# drone.net
KiCad netlist of a schematic drawn in Altium Designer
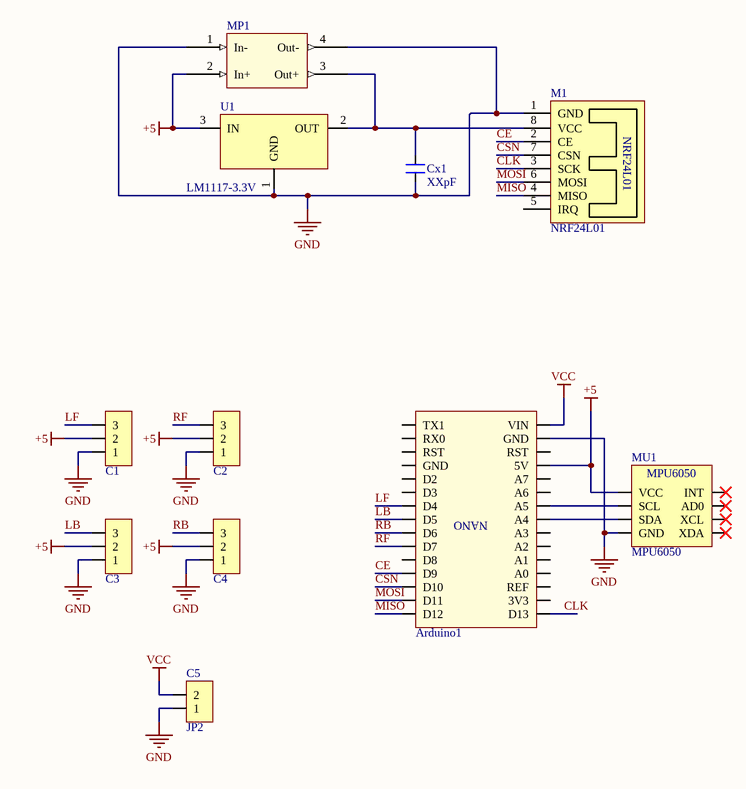
[diagram p0: drone.SchDoc]

(export (version "E")
  (design (tool "Eeschema 10.0.6"))
  (components
    (comp (ref "Arduino1")
      (value "Arduino Nano")
      (footprint "Arduino Nano")
      (description "Arduino NANO")
      (libsource (lib "LIBRARY") (part "Arduino Nano"))
    )
    (comp (ref "C1")
      (value "JP3")
      (footprint "JP3-C1T")
      (description "WR-PHD 2.54 mm Angled Socket Header")
      (fields
        (field (name "MANUFACTURER") "Würth Elektronik eiSos GmbH")
        (field (name "PARTNO") "613003143121")
        (field (name "CREATED BY") "Karrer Zheng")
      )
      (libsource (lib "LIBRARY") (part "JP3"))
    )
    (comp (ref "C2")
      (value "JP3")
      (footprint "JP3-C1T")
      (description "WR-PHD 2.54 mm Angled Socket Header")
      (fields
        (field (name "MANUFACTURER") "Würth Elektronik eiSos GmbH")
        (field (name "PARTNO") "613003143121")
        (field (name "CREATED BY") "Karrer Zheng")
      )
      (libsource (lib "LIBRARY") (part "JP3"))
    )
    (comp (ref "C3")
      (value "JP3")
      (footprint "JP3-C1T")
      (description "WR-PHD 2.54 mm Angled Socket Header")
      (fields
        (field (name "MANUFACTURER") "Würth Elektronik eiSos GmbH")
        (field (name "PARTNO") "613003143121")
        (field (name "CREATED BY") "Karrer Zheng")
      )
      (libsource (lib "LIBRARY") (part "JP3"))
    )
    (comp (ref "C4")
      (value "JP3")
      (footprint "JP3-C1T")
      (description "WR-PHD 2.54 mm Angled Socket Header")
      (fields
        (field (name "MANUFACTURER") "Würth Elektronik eiSos GmbH")
        (field (name "PARTNO") "613003143121")
        (field (name "CREATED BY") "Karrer Zheng")
      )
      (libsource (lib "LIBRARY") (part "JP3"))
    )
    (comp (ref "C5")
      (value "JP2")
      (footprint "JP2-C1T")
      (description "WR-PHD 2.54 mm Angled Socket Header")
      (fields
        (field (name "MANUFACTURER") "Würth Elektronik eiSos GmbH")
        (field (name "PARTNO") "613002143121")
        (field (name "CREATED BY") "Karrer Zheng")
      )
      (libsource (lib "LIBRARY") (part "JP2"))
    )
    (comp (ref "Cx1") (value "XXpF") (footprint "CN-SMD-1206") (libsource (lib "LIBRARY") (part "CN")))
    (comp (ref "M1") (value "NRF24L01") (footprint "NRF24L01") (libsource (lib "LIBRARY") (part "NRF24L01")))
    (comp (ref "MP1")
      (value "MP2307 DC-DC Switching Buck Step-Down Module")
      (footprint "Mini360")
      (libsource (lib "0503") (part "MP2307 Module"))
    )
    (comp (ref "MU1")
      (value "MPU6050")
      (footprint "MPU6050")
      (fields
        (field (name "MANUFACTURER") "Würth Elektronik eiSos GmbH")
        (field (name "PARTNO") "613004143121")
        (field (name "CREATED BY") "Karrer Zheng")
      )
      (libsource (lib "LIBRARY") (part "MPU6050"))
    )
    (comp (ref "U1")
      (value "LM1117-3.3V")
      (footprint "SOT223")
      (description "800mA Low-Dropout Linear Regulator")
      (fields (field (name "CREATOR") "Nguyen Ba Bien"))
      (libsource (lib "LIBRARY") (part "LM1117"))
    )
  )
  (nets
    (net (code "1") (name "+5") (class "Default")
      (node (ref "Arduino1") (pin "5V") (pinfunction "5V_5V") (pintype "passive"))
      (node (ref "C1") (pin "2") (pinfunction "2_2") (pintype "passive"))
      (node (ref "C2") (pin "2") (pinfunction "2_2") (pintype "passive"))
      (node (ref "C3") (pin "2") (pinfunction "2_2") (pintype "passive"))
      (node (ref "C4") (pin "2") (pinfunction "2_2") (pintype "passive"))
      (node (ref "MP1") (pin "2") (pinfunction "In+_2") (pintype "input"))
      (node (ref "MU1") (pin "1") (pinfunction "VCC_1") (pintype "passive"))
      (node (ref "U1") (pin "3") (pinfunction "IN_3") (pintype "passive"))
    )
    (net (code "2") (name "/CE") (class "Default")
      (node (ref "Arduino1") (pin "D9") (pinfunction "D9_D9") (pintype "passive"))
      (node (ref "M1") (pin "2") (pinfunction "CE_2") (pintype "passive"))
    )
    (net (code "3") (name "/CLK") (class "Default")
      (node (ref "Arduino1") (pin "D13") (pinfunction "D13_D13") (pintype "passive"))
      (node (ref "M1") (pin "3") (pinfunction "SCK_3") (pintype "passive"))
    )
    (net (code "4") (name "/CSN") (class "Default")
      (node (ref "Arduino1") (pin "D10") (pinfunction "D10_D10") (pintype "passive"))
      (node (ref "M1") (pin "7") (pinfunction "CSN_7") (pintype "passive"))
    )
    (net (code "5") (name "/LB") (class "Default")
      (node (ref "Arduino1") (pin "D5") (pinfunction "D5_D5") (pintype "passive"))
      (node (ref "C3") (pin "3") (pinfunction "3_3") (pintype "passive"))
    )
    (net (code "6") (name "/LF") (class "Default")
      (node (ref "Arduino1") (pin "D4") (pinfunction "D4_D4") (pintype "passive"))
      (node (ref "C1") (pin "3") (pinfunction "3_3") (pintype "passive"))
    )
    (net (code "7") (name "/MISO") (class "Default")
      (node (ref "Arduino1") (pin "D12") (pinfunction "D12_D12") (pintype "passive"))
      (node (ref "M1") (pin "4") (pinfunction "MISO_4") (pintype "passive"))
    )
    (net (code "8") (name "/MOSI") (class "Default")
      (node (ref "Arduino1") (pin "D11") (pinfunction "D11_D11") (pintype "passive"))
      (node (ref "M1") (pin "6") (pinfunction "MOSI_6") (pintype "passive"))
    )
    (net (code "9") (name "/RB") (class "Default")
      (node (ref "Arduino1") (pin "D6") (pinfunction "D6_D6") (pintype "passive"))
      (node (ref "C4") (pin "3") (pinfunction "3_3") (pintype "passive"))
    )
    (net (code "10") (name "/RF") (class "Default")
      (node (ref "Arduino1") (pin "D7") (pinfunction "D7_D7") (pintype "passive"))
      (node (ref "C2") (pin "3") (pinfunction "3_3") (pintype "passive"))
    )
    (net (code "11") (name "GND") (class "Default")
      (node (ref "Arduino1") (pin "GND") (pinfunction "GND_GND") (pintype "passive"))
      (node (ref "C1") (pin "1") (pinfunction "1_1") (pintype "passive"))
      (node (ref "C2") (pin "1") (pinfunction "1_1") (pintype "passive"))
      (node (ref "C3") (pin "1") (pinfunction "1_1") (pintype "passive"))
      (node (ref "C4") (pin "1") (pinfunction "1_1") (pintype "passive"))
      (node (ref "C5") (pin "1") (pinfunction "1_1") (pintype "passive"))
      (node (ref "Cx1") (pin "1") (pinfunction "1_1") (pintype "passive"))
      (node (ref "M1") (pin "1") (pinfunction "GND_1") (pintype "passive"))
      (node (ref "MP1") (pin "1") (pinfunction "In-_1") (pintype "input"))
      (node (ref "MP1") (pin "4") (pinfunction "Out-_4") (pintype "output"))
      (node (ref "MU1") (pin "2") (pinfunction "GND_2") (pintype "passive"))
      (node (ref "U1") (pin "1") (pinfunction "GND_1") (pintype "passive"))
    )
    (net (code "12") (name "Net-(M1-VCC)") (class "Default")
      (node (ref "Cx1") (pin "2") (pinfunction "2_2") (pintype "passive"))
      (node (ref "M1") (pin "8") (pinfunction "VCC_8") (pintype "passive"))
      (node (ref "MP1") (pin "3") (pinfunction "Out+_3") (pintype "output"))
      (node (ref "U1") (pin "2") (pinfunction "OUT_2") (pintype "passive"))
    )
    (net (code "13") (name "Net-(MU1-SCL)") (class "Default")
      (node (ref "Arduino1") (pin "A5") (pinfunction "A5_A5") (pintype "passive"))
      (node (ref "MU1") (pin "3") (pinfunction "SCL_3") (pintype "passive"))
    )
    (net (code "14") (name "Net-(MU1-SDA)") (class "Default")
      (node (ref "Arduino1") (pin "A4") (pinfunction "A4_A4") (pintype "passive"))
      (node (ref "MU1") (pin "4") (pinfunction "SDA_4") (pintype "passive"))
    )
    (net (code "15") (name "VCC") (class "Default")
      (node (ref "Arduino1") (pin "VIN") (pinfunction "VIN_VIN") (pintype "passive"))
      (node (ref "C5") (pin "2") (pinfunction "2_2") (pintype "passive"))
    )
    (net (code "16") (name "unconnected-(Arduino1-Pad3V3)") (class "Default")
      (node (ref "Arduino1") (pin "3V3") (pinfunction "3V3_3V3") (pintype "passive"))
    )
    (net (code "17") (name "unconnected-(Arduino1-PadA0)") (class "Default")
      (node (ref "Arduino1") (pin "A0") (pinfunction "A0_A0") (pintype "passive"))
    )
    (net (code "18") (name "unconnected-(Arduino1-PadA1)") (class "Default")
      (node (ref "Arduino1") (pin "A1") (pinfunction "A1_A1") (pintype "passive"))
    )
    (net (code "19") (name "unconnected-(Arduino1-PadA2)") (class "Default")
      (node (ref "Arduino1") (pin "A2") (pinfunction "A2_A2") (pintype "passive"))
    )
    (net (code "20") (name "unconnected-(Arduino1-PadA3)") (class "Default")
      (node (ref "Arduino1") (pin "A3") (pinfunction "A3_A3") (pintype "passive"))
    )
    (net (code "21") (name "unconnected-(Arduino1-PadA6)") (class "Default")
      (node (ref "Arduino1") (pin "A6") (pinfunction "A6_A6") (pintype "passive"))
    )
    (net (code "22") (name "unconnected-(Arduino1-PadA7)") (class "Default")
      (node (ref "Arduino1") (pin "A7") (pinfunction "A7_A7") (pintype "passive"))
    )
    (net (code "23") (name "unconnected-(Arduino1-PadD2)") (class "Default")
      (node (ref "Arduino1") (pin "D2") (pinfunction "D2_D2") (pintype "passive"))
    )
    (net (code "24") (name "unconnected-(Arduino1-PadD3)") (class "Default")
      (node (ref "Arduino1") (pin "D3") (pinfunction "D3_D3") (pintype "passive"))
    )
    (net (code "25") (name "unconnected-(Arduino1-PadD8)") (class "Default")
      (node (ref "Arduino1") (pin "D8") (pinfunction "D8_D8") (pintype "passive"))
    )
    (net (code "26") (name "unconnected-(Arduino1-PadGND)") (class "Default")
      (node (ref "Arduino1") (pin "GND") (pinfunction "GND_GND") (pintype "passive"))
    )
    (net (code "27") (name "unconnected-(Arduino1-PadREF)") (class "Default")
      (node (ref "Arduino1") (pin "REF") (pinfunction "REF_REF") (pintype "passive"))
    )
    (net (code "28") (name "unconnected-(Arduino1-PadRST)") (class "Default")
      (node (ref "Arduino1") (pin "RST") (pinfunction "RST_RST") (pintype "passive"))
    )
    (net (code "29") (name "unconnected-(Arduino1-PadRST)_1") (class "Default")
      (node (ref "Arduino1") (pin "RST") (pinfunction "RST_RST") (pintype "passive"))
    )
    (net (code "30") (name "unconnected-(Arduino1-PadRX0)") (class "Default")
      (node (ref "Arduino1") (pin "RX0") (pinfunction "RX0_RX0") (pintype "passive"))
    )
    (net (code "31") (name "unconnected-(Arduino1-PadTX1)") (class "Default")
      (node (ref "Arduino1") (pin "TX1") (pinfunction "TX1_TX1") (pintype "passive"))
    )
    (net (code "32") (name "unconnected-(M1-IRQ-Pad5)") (class "Default")
      (node (ref "M1") (pin "5") (pinfunction "IRQ_5") (pintype "passive"))
    )
    (net (code "33") (name "unconnected-(MU1-AD0-Pad7)") (class "Default")
      (node (ref "MU1") (pin "7") (pinfunction "AD0_7") (pintype "passive+no_connect"))
    )
    (net (code "34") (name "unconnected-(MU1-INT-Pad8)") (class "Default")
      (node (ref "MU1") (pin "8") (pinfunction "INT_8") (pintype "passive+no_connect"))
    )
    (net (code "35") (name "unconnected-(MU1-XCL-Pad6)") (class "Default")
      (node (ref "MU1") (pin "6") (pinfunction "XCL_6") (pintype "passive+no_connect"))
    )
    (net (code "36") (name "unconnected-(MU1-XDA-Pad5)") (class "Default")
      (node (ref "MU1") (pin "5") (pinfunction "XDA_5") (pintype "passive+no_connect"))
    )
  )
)
